# rgb-nir-uv-breakout.net
KiCad netlist of a schematic drawn in EAGLE
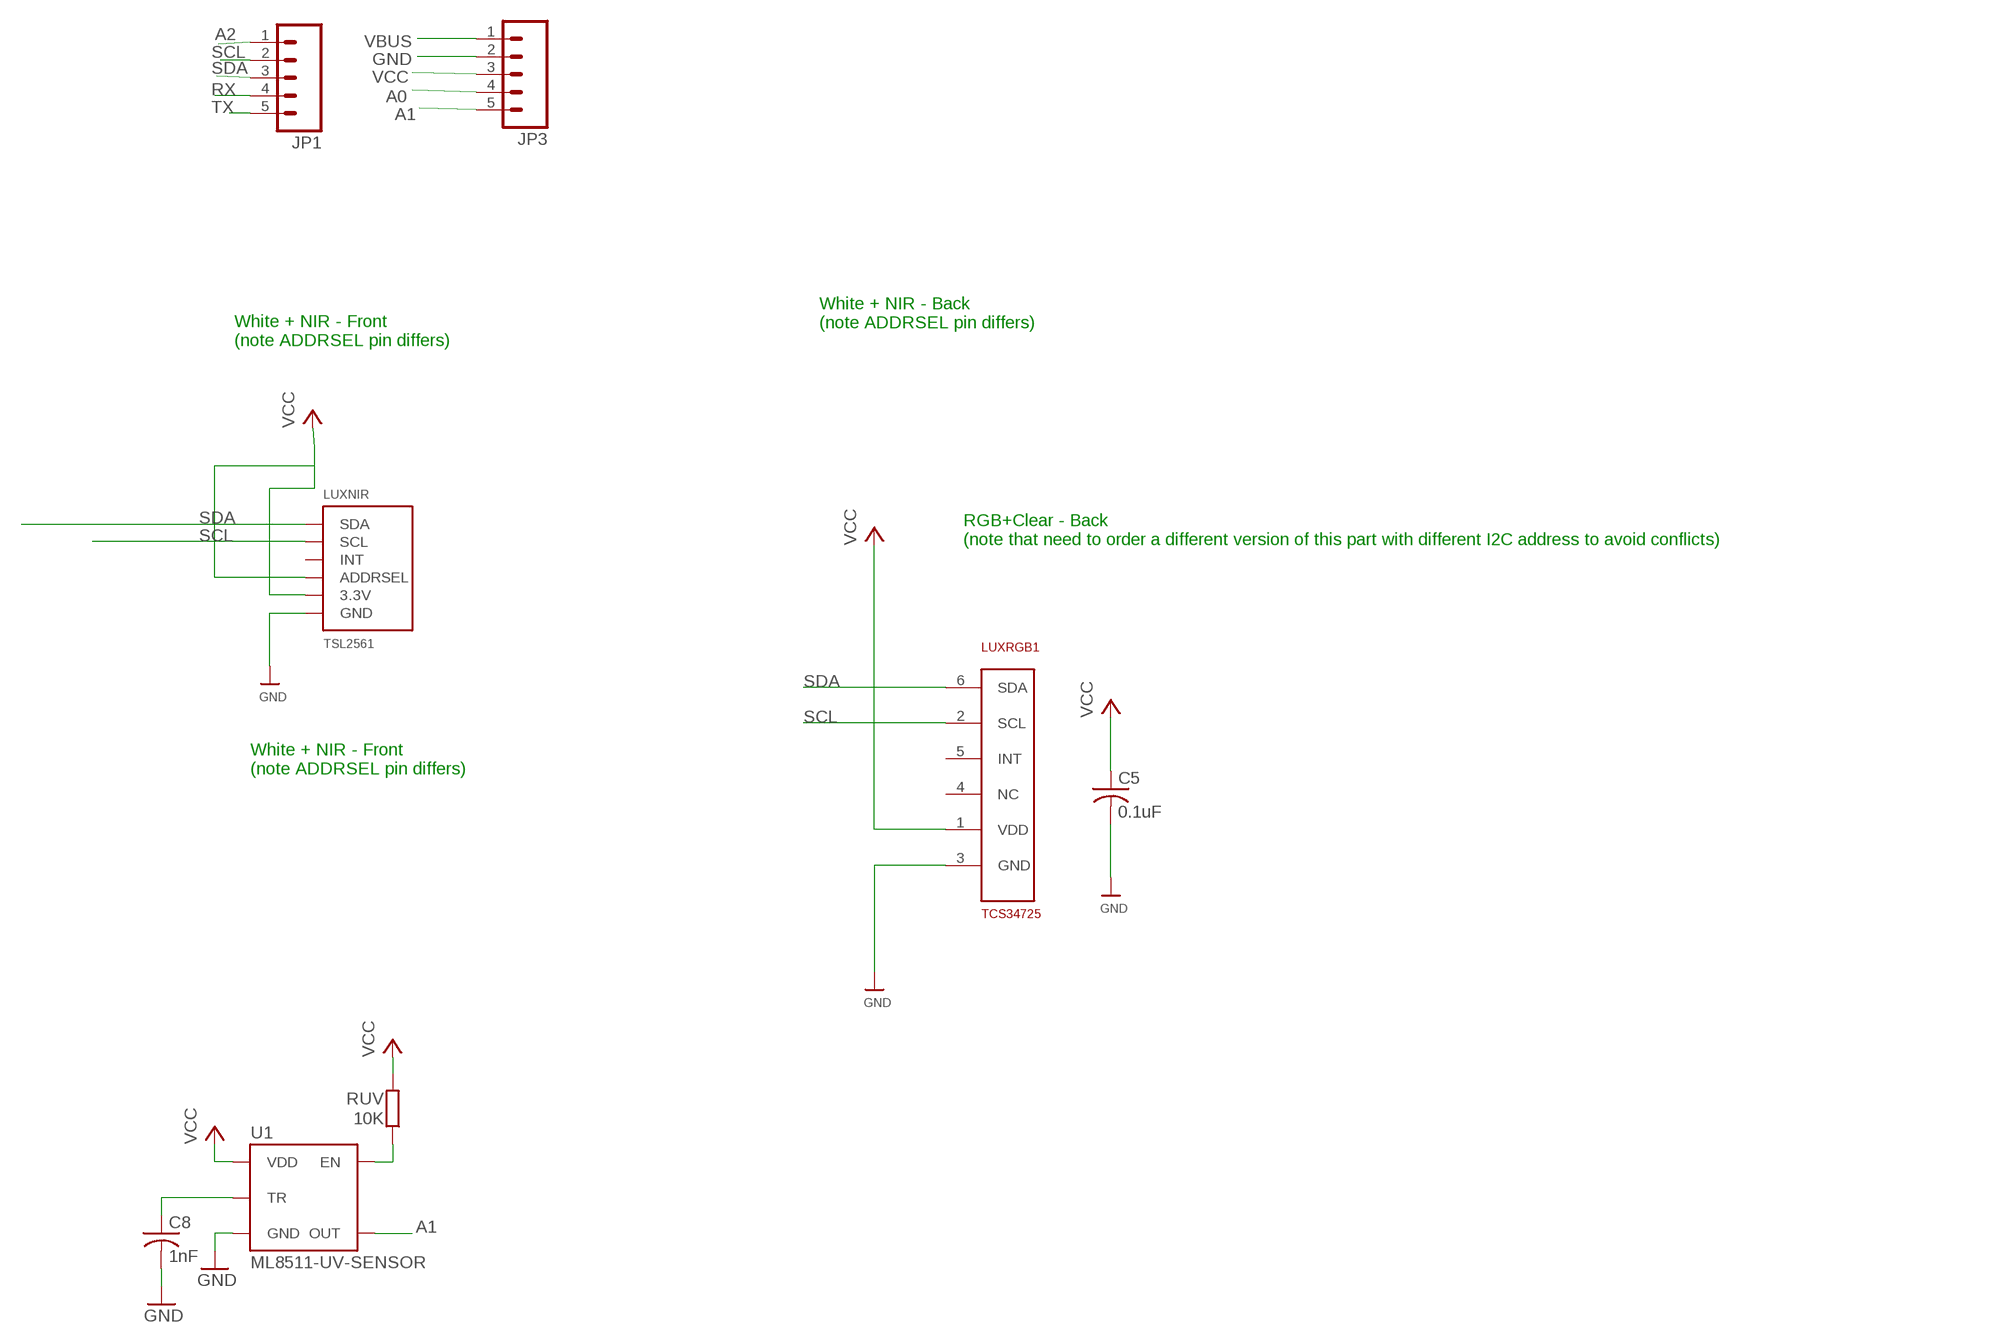
[diagram p0: schematic, sheet 1]

(export (version "E")
  (design (tool "Eeschema 10.0.6"))
  (components
    (comp (ref "C5")
      (value "0.1uF")
      (footprint "eagle-import:C0805")
      (libsource (lib "eagle-import") (part "C-USC0805"))
    )
    (comp (ref "C8")
      (value "1nF")
      (footprint "eagle-import:C0805")
      (libsource (lib "eagle-import") (part "C-USC0805"))
    )
    (comp (ref "JP1")
      (value "M05LOCK")
      (footprint "eagle-import:1X05_LOCK")
      (libsource (lib "eagle-import") (part "M05LOCK"))
    )
    (comp (ref "JP3")
      (value "M05LOCK")
      (footprint "eagle-import:1X05_LOCK")
      (libsource (lib "eagle-import") (part "M05LOCK"))
    )
    (comp (ref "LUXNIR")
      (value "TSL2561")
      (footprint "eagle-import:TSL2561_FN@1")
      (libsource (lib "eagle-import") (part "TSL2561"))
    )
    (comp (ref "LUXRGB1")
      (value "TCS34725")
      (footprint "eagle-import:DFN-6")
      (libsource (lib "eagle-import") (part "TCS34725"))
    )
    (comp (ref "RUV")
      (value "10K")
      (footprint "eagle-import:R0805")
      (libsource (lib "eagle-import") (part "R-EU_R0805"))
    )
    (comp (ref "U1")
      (value "ML8511-UV-SENSOR")
      (footprint "eagle-import:ML8511")
      (libsource (lib "eagle-import") (part "ML8511-UV-SENSORSMD"))
    )
  )
  (nets
    (net (code "1") (name "/A0") (class "Default")
      (node (ref "JP3") (pin "4") (pinfunction "4_4") (pintype "passive"))
    )
    (net (code "2") (name "/A1") (class "Default")
      (node (ref "JP3") (pin "5") (pinfunction "5_5") (pintype "passive"))
      (node (ref "U1") (pin "8") (pinfunction "OUT_8") (pintype "output"))
    )
    (net (code "3") (name "/A2") (class "Default")
      (node (ref "JP1") (pin "1") (pinfunction "1_1") (pintype "passive"))
    )
    (net (code "4") (name "/RX") (class "Default")
      (node (ref "JP1") (pin "4") (pinfunction "4_4") (pintype "passive"))
    )
    (net (code "5") (name "/SCL") (class "Default")
      (node (ref "JP1") (pin "2") (pinfunction "2_2") (pintype "passive"))
      (node (ref "LUXNIR") (pin "CLK") (pinfunction "SCL_CLK") (pintype "bidirectional"))
      (node (ref "LUXRGB1") (pin "2") (pinfunction "SCL_2") (pintype "bidirectional"))
    )
    (net (code "6") (name "/SDA") (class "Default")
      (node (ref "JP1") (pin "3") (pinfunction "3_3") (pintype "passive"))
      (node (ref "LUXNIR") (pin "DATA") (pinfunction "SDA_DATA") (pintype "bidirectional"))
      (node (ref "LUXRGB1") (pin "6") (pinfunction "SDA_6") (pintype "bidirectional"))
    )
    (net (code "7") (name "/TX") (class "Default")
      (node (ref "JP1") (pin "5") (pinfunction "5_5") (pintype "passive"))
    )
    (net (code "8") (name "/VBUS") (class "Default")
      (node (ref "JP3") (pin "1") (pinfunction "1_1") (pintype "passive"))
    )
    (net (code "9") (name "GND") (class "Default")
      (node (ref "C5") (pin "2") (pinfunction "2_2") (pintype "passive"))
      (node (ref "C8") (pin "2") (pinfunction "2_2") (pintype "passive"))
      (node (ref "JP3") (pin "2") (pinfunction "2_2") (pintype "passive"))
      (node (ref "LUXNIR") (pin "VSS") (pinfunction "GND_VSS") (pintype "bidirectional"))
      (node (ref "LUXRGB1") (pin "3") (pinfunction "GND_3") (pintype "bidirectional"))
      (node (ref "U1") (pin "5") (pinfunction "GND_5") (pintype "power_in"))
    )
    (net (code "10") (name "Net-(U1-EN)") (class "Default")
      (node (ref "RUV") (pin "1") (pinfunction "1_1") (pintype "passive"))
      (node (ref "U1") (pin "4") (pinfunction "EN_4") (pintype "input"))
    )
    (net (code "11") (name "Net-(U1-TR)") (class "Default")
      (node (ref "C8") (pin "1") (pinfunction "1_1") (pintype "passive"))
      (node (ref "U1") (pin "10") (pinfunction "TR_10") (pintype "power_in"))
    )
    (net (code "12") (name "VCC") (class "Default")
      (node (ref "C5") (pin "1") (pinfunction "1_1") (pintype "passive"))
      (node (ref "JP3") (pin "3") (pinfunction "3_3") (pintype "passive"))
      (node (ref "LUXNIR") (pin "ADR") (pinfunction "ADDRSEL_ADR") (pintype "bidirectional"))
      (node (ref "LUXNIR") (pin "VDD") (pinfunction "3.3V_VDD") (pintype "bidirectional"))
      (node (ref "LUXRGB1") (pin "1") (pinfunction "VDD_1") (pintype "bidirectional"))
      (node (ref "RUV") (pin "2") (pinfunction "2_2") (pintype "passive"))
      (node (ref "U1") (pin "7") (pinfunction "VDD_7") (pintype "power_in"))
    )
    (net (code "13") (name "unconnected-(LUXNIR-PadINT)") (class "Default")
      (node (ref "LUXNIR") (pin "INT") (pinfunction "INT_INT") (pintype "bidirectional"))
    )
    (net (code "14") (name "unconnected-(LUXRGB1-INT-Pad5)") (class "Default")
      (node (ref "LUXRGB1") (pin "5") (pinfunction "INT_5") (pintype "bidirectional"))
    )
    (net (code "15") (name "unconnected-(LUXRGB1-NC-Pad4)") (class "Default")
      (node (ref "LUXRGB1") (pin "4") (pinfunction "NC_4") (pintype "bidirectional"))
    )
  )
)
